# 2101_Version.net
KiCad netlist of a schematic drawn in Altium Designer
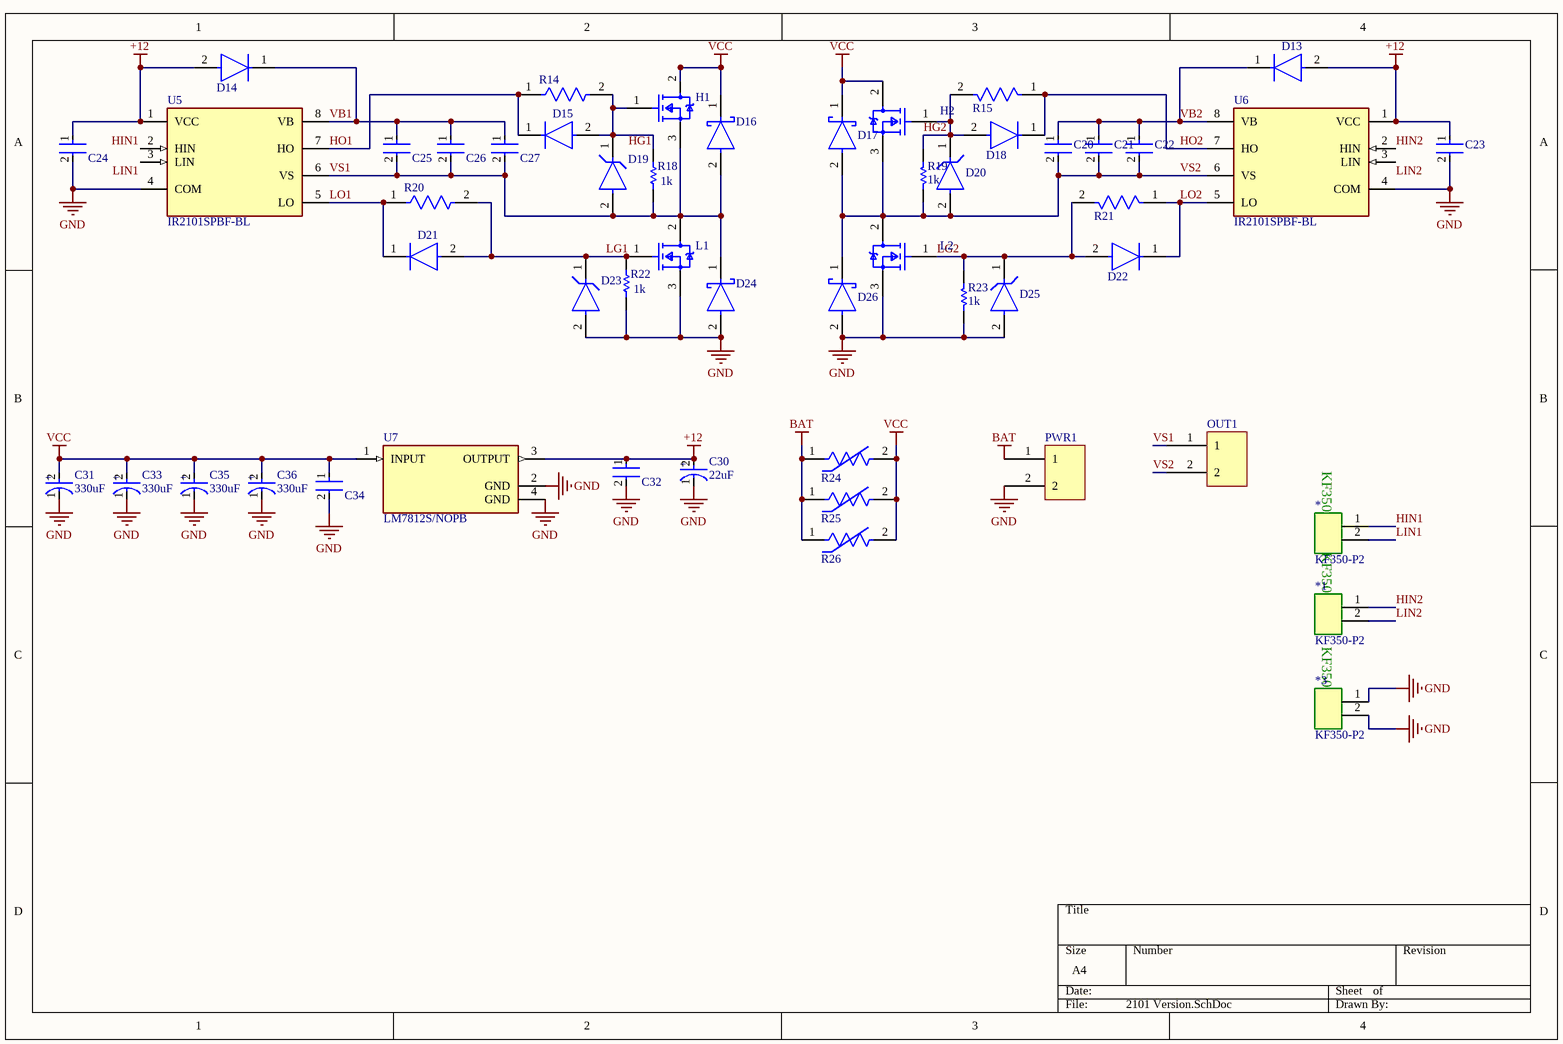
[diagram p0: 2101 Version.SchDoc]

(export (version "E")
  (design (tool "Eeschema 10.0.6"))
  (components
    (comp (ref "*")
      (value "KF350-P2")
      (footprint "New footprint 1")
      (description "3.5mm mini klemens")
      (libsource (lib "ITU Autobee") (part "New symbol 1"))
    )
    (comp (ref "*1")
      (value "KF350-P2")
      (footprint "New footprint 1")
      (description "3.5mm mini klemens")
      (libsource (lib "ITU Autobee") (part "New symbol 1"))
    )
    (comp (ref "*3")
      (value "KF350-P2")
      (footprint "New footprint 1")
      (description "3.5mm mini klemens")
      (libsource (lib "ITU Autobee") (part "New symbol 1"))
    )
    (comp (ref "C20")
      (value "12061C474KAT2A")
      (footprint "FP-1206-L_3_2_0_2-W_1_6_0-IPC_B")
      (description "1206 470 nF 100 V ±10 % Tolerance X7R Surface Mount Multilayer Ceramic Capacitor")
      (libsource (lib "ITU Autobee") (part "b4654b650e69147ec39a6b967a45e02"))
    )
    (comp (ref "C21")
      (value "12061C474KAT2A")
      (footprint "FP-1206-L_3_2_0_2-W_1_6_0-IPC_B")
      (description "1206 470 nF 100 V ±10 % Tolerance X7R Surface Mount Multilayer Ceramic Capacitor")
      (libsource (lib "ITU Autobee") (part "b4654b650e69147ec39a6b967a45e02"))
    )
    (comp (ref "C22")
      (value "12061C474KAT2A")
      (footprint "FP-1206-L_3_2_0_2-W_1_6_0-IPC_B")
      (description "1206 470 nF 100 V ±10 % Tolerance X7R Surface Mount Multilayer Ceramic Capacitor")
      (libsource (lib "ITU Autobee") (part "b4654b650e69147ec39a6b967a45e02"))
    )
    (comp (ref "C23")
      (value "12065C104KAT2A")
      (footprint "FP-1206-L_3_2_0_2-W_1_6_0-IPC_B")
      (description "Ceramic capacitor SMD-1206 100nF /50V X7R# K +-10%, AVX, RoHS, /4000 reel/")
      (libsource (lib "ITU Autobee") (part "02cd4be3c70576c341d710602a673aa"))
    )
    (comp (ref "C24")
      (value "12065C104KAT2A")
      (footprint "FP-1206-L_3_2_0_2-W_1_6_0-IPC_B")
      (description "Ceramic capacitor SMD-1206 100nF /50V X7R# K +-10%, AVX, RoHS, /4000 reel/")
      (libsource (lib "ITU Autobee") (part "02cd4be3c70576c341d710602a673aa"))
    )
    (comp (ref "C25")
      (value "12061C474KAT2A")
      (footprint "FP-1206-L_3_2_0_2-W_1_6_0-IPC_B")
      (description "1206 470 nF 100 V ±10 % Tolerance X7R Surface Mount Multilayer Ceramic Capacitor")
      (libsource (lib "ITU Autobee") (part "b4654b650e69147ec39a6b967a45e02"))
    )
    (comp (ref "C26")
      (value "12061C474KAT2A")
      (footprint "FP-1206-L_3_2_0_2-W_1_6_0-IPC_B")
      (description "1206 470 nF 100 V ±10 % Tolerance X7R Surface Mount Multilayer Ceramic Capacitor")
      (libsource (lib "ITU Autobee") (part "b4654b650e69147ec39a6b967a45e02"))
    )
    (comp (ref "C27")
      (value "12061C474KAT2A")
      (footprint "FP-1206-L_3_2_0_2-W_1_6_0-IPC_B")
      (description "1206 470 nF 100 V ±10 % Tolerance X7R Surface Mount Multilayer Ceramic Capacitor")
      (libsource (lib "ITU Autobee") (part "b4654b650e69147ec39a6b967a45e02"))
    )
    (comp (ref "C30")
      (value "22uF")
      (footprint "FP-SD-MFG")
      (description "Cap Aluminum 22uF 35V 20% (6.3 X 5.4mm) SMD 60mA 2000h 85 C T/R")
      (fields (field (name "Comment") "EEE-1VA220SP 22uF 50V"))
      (libsource (lib "ITU Autobee") (part "a00bbbee19879c290e62620ae7e47b1"))
    )
    (comp (ref "C31")
      (value "330uF")
      (footprint "FP-UWT1V331MNL1GS-MFG")
      (description "Aluminum Electrolytic Capacitor, 330uF 35 V, WT Series 1000h 10 (Dia.) x 10mm")
      (fields (field (name "Comment") "UWT1V331MNL1GS 330uF 35V smd"))
      (libsource (lib "ITU Autobee") (part "203bc49f2ac43e59fd269a8c329ed05"))
    )
    (comp (ref "C32")
      (value "12065C104KAT2A")
      (footprint "FP-1206-L_3_2_0_2-W_1_6_0-IPC_B")
      (description "Ceramic capacitor SMD-1206 100nF /50V X7R# K +-10%, AVX, RoHS, /4000 reel/")
      (libsource (lib "ITU Autobee") (part "02cd4be3c70576c341d710602a673aa"))
    )
    (comp (ref "C33")
      (value "330uF")
      (footprint "FP-UWT1V331MNL1GS-MFG")
      (description "Aluminum Electrolytic Capacitor, 330uF 35 V, WT Series 1000h 10 (Dia.) x 10mm")
      (fields (field (name "Comment") "UWT1V331MNL1GS 330uF 35V smd"))
      (libsource (lib "ITU Autobee") (part "203bc49f2ac43e59fd269a8c329ed05"))
    )
    (comp (ref "C34")
      (value "12065C104KAT2A")
      (footprint "FP-1206-L_3_2_0_2-W_1_6_0-IPC_B")
      (description "Ceramic capacitor SMD-1206 100nF /50V X7R# K +-10%, AVX, RoHS, /4000 reel/")
      (libsource (lib "ITU Autobee") (part "02cd4be3c70576c341d710602a673aa"))
    )
    (comp (ref "C35")
      (value "330uF")
      (footprint "FP-UWT1V331MNL1GS-MFG")
      (description "Aluminum Electrolytic Capacitor, 330uF 35 V, WT Series 1000h 10 (Dia.) x 10mm")
      (fields (field (name "Comment") "UWT1V331MNL1GS 330uF 35V smd"))
      (libsource (lib "ITU Autobee") (part "203bc49f2ac43e59fd269a8c329ed05"))
    )
    (comp (ref "C36")
      (value "330uF")
      (footprint "FP-UWT1V331MNL1GS-MFG")
      (description "Aluminum Electrolytic Capacitor, 330uF 35 V, WT Series 1000h 10 (Dia.) x 10mm")
      (fields (field (name "Comment") "UWT1V331MNL1GS 330uF 35V smd"))
      (libsource (lib "ITU Autobee") (part "203bc49f2ac43e59fd269a8c329ed05"))
    )
    (comp (ref "D13")
      (value "MURS120T3G")
      (footprint "FP-403A-03-MFG")
      (description "VR=200V IF=2A Trr=35ns")
      (libsource (lib "ITU Autobee") (part "d7152d700b627762746794eb795d46e"))
    )
    (comp (ref "D14")
      (value "MURS120T3G")
      (footprint "FP-403A-03-MFG")
      (description "VR=200V IF=2A Trr=35ns")
      (libsource (lib "ITU Autobee") (part "d7152d700b627762746794eb795d46e"))
    )
    (comp (ref "D15")
      (value "MURS120T3G")
      (footprint "FP-403A-03-MFG")
      (description "VR=200V IF=2A Trr=35ns")
      (libsource (lib "ITU Autobee") (part "d7152d700b627762746794eb795d46e"))
    )
    (comp (ref "D16")
      (value "SS34-E3/57T")
      (footprint "FP-95402-MFG")
      (description "DIODE SCHOTTKY 40V 3A DO214AB")
      (libsource (lib "ITU Autobee") (part "1d6ec82d83fb6aee721767c19dac4b9"))
    )
    (comp (ref "D17")
      (value "SS34-E3/57T")
      (footprint "FP-95402-MFG")
      (description "DIODE SCHOTTKY 40V 3A DO214AB")
      (libsource (lib "ITU Autobee") (part "1d6ec82d83fb6aee721767c19dac4b9"))
    )
    (comp (ref "D18")
      (value "MURS120T3G")
      (footprint "FP-403A-03-MFG")
      (description "VR=200V IF=2A Trr=35ns")
      (libsource (lib "ITU Autobee") (part "d7152d700b627762746794eb795d46e"))
    )
    (comp (ref "D19")
      (value "TZMC3V3-GS08")
      (footprint "FP-6_560-5005_01-4-MFG")
      (description "DIODE ZENER 3.3V 500MW SOD80")
      (libsource (lib "ITU Autobee") (part "f813f71cba58e380607f5dd3caf9714"))
    )
    (comp (ref "D20")
      (value "TZMC3V3-GS08")
      (footprint "FP-6_560-5005_01-4-MFG")
      (description "DIODE ZENER 3.3V 500MW SOD80")
      (libsource (lib "ITU Autobee") (part "f813f71cba58e380607f5dd3caf9714"))
    )
    (comp (ref "D21")
      (value "MURS120T3G")
      (footprint "FP-403A-03-MFG")
      (description "VR=200V IF=2A Trr=35ns")
      (libsource (lib "ITU Autobee") (part "d7152d700b627762746794eb795d46e"))
    )
    (comp (ref "D22")
      (value "MURS120T3G")
      (footprint "FP-403A-03-MFG")
      (description "VR=200V IF=2A Trr=35ns")
      (libsource (lib "ITU Autobee") (part "d7152d700b627762746794eb795d46e"))
    )
    (comp (ref "D23")
      (value "TZMC3V3-GS08")
      (footprint "FP-6_560-5005_01-4-MFG")
      (description "DIODE ZENER 3.3V 500MW SOD80")
      (libsource (lib "ITU Autobee") (part "f813f71cba58e380607f5dd3caf9714"))
    )
    (comp (ref "D24")
      (value "SS34-E3/57T")
      (footprint "FP-95402-MFG")
      (description "DIODE SCHOTTKY 40V 3A DO214AB")
      (libsource (lib "ITU Autobee") (part "1d6ec82d83fb6aee721767c19dac4b9"))
    )
    (comp (ref "D25")
      (value "TZMC3V3-GS08")
      (footprint "FP-6_560-5005_01-4-MFG")
      (description "DIODE ZENER 3.3V 500MW SOD80")
      (libsource (lib "ITU Autobee") (part "f813f71cba58e380607f5dd3caf9714"))
    )
    (comp (ref "D26")
      (value "SS34-E3/57T")
      (footprint "FP-95402-MFG")
      (description "DIODE SCHOTTKY 40V 3A DO214AB")
      (libsource (lib "ITU Autobee") (part "1d6ec82d83fb6aee721767c19dac4b9"))
    )
    (comp (ref "H1")
      (value "IRF3205STRLPBF")
      (footprint "FP-PG-TO263-3-MFG")
      (description "MOSFET N-CH 55V 110A D2PAK")
      (libsource (lib "ITU Autobee") (part "b09f7f152735e370c1ea22a33fa83d6"))
    )
    (comp (ref "H2")
      (value "IRF3205STRLPBF")
      (footprint "FP-PG-TO263-3-MFG")
      (description "MOSFET N-CH 55V 110A D2PAK")
      (libsource (lib "ITU Autobee") (part "b09f7f152735e370c1ea22a33fa83d6"))
    )
    (comp (ref "L1")
      (value "IRF3205STRLPBF")
      (footprint "FP-PG-TO263-3-MFG")
      (description "MOSFET N-CH 55V 110A D2PAK")
      (libsource (lib "ITU Autobee") (part "b09f7f152735e370c1ea22a33fa83d6"))
    )
    (comp (ref "L2")
      (value "IRF3205STRLPBF")
      (footprint "FP-PG-TO263-3-MFG")
      (description "MOSFET N-CH 55V 110A D2PAK")
      (libsource (lib "ITU Autobee") (part "b09f7f152735e370c1ea22a33fa83d6"))
    )
    (comp (ref "OUT1")
      (value "2 pin terminal klemens")
      (footprint "New footprint 1")
      (description "2 pin terminal klemens pin aralığı 200 mil")
      (libsource (lib "ITU Autobee") (part "2 pin terminal klemens schematic"))
    )
    (comp (ref "PWR1")
      (value "2 pin terminal klemens")
      (footprint "New footprint 1")
      (description "2 pin terminal klemens pin aralığı 200 mil")
      (libsource (lib "ITU Autobee") (part "2 pin terminal klemens schematic"))
    )
    (comp (ref "R14")
      (value "RC1206JR-0710RL")
      (footprint "FP-RC1206-0_65-MFG")
      (description "Res General Purpose Thick Film 1206 10 Ohm 5% 1/4W ±200ppm/°C Molded SMD Paper T/R")
      (libsource (lib "ITU Autobee") (part "8db39607336c341a927600551d01821"))
    )
    (comp (ref "R15")
      (value "RC1206JR-0710RL")
      (footprint "FP-RC1206-0_65-MFG")
      (description "Res General Purpose Thick Film 1206 10 Ohm 5% 1/4W ±200ppm/°C Molded SMD Paper T/R")
      (libsource (lib "ITU Autobee") (part "8db39607336c341a927600551d01821"))
    )
    (comp (ref "R18")
      (value "1k")
      (footprint "RESC3116X70X50ML13T20")
      (description "Chip Resistor, 1 KOhm, +/- 1%, 0.25 W, -55 to 155 degC, 1206 (3216 Metric)")
      (fields (field (name "TOLERANCE") "1%") (field (name "POWER") "250mW"))
      (libsource (lib "ITU Autobee") (part "RES-2"))
    )
    (comp (ref "R19")
      (value "1k")
      (footprint "RESC3116X70X50ML13T20")
      (description "Chip Resistor, 1 KOhm, +/- 1%, 0.25 W, -55 to 155 degC, 1206 (3216 Metric)")
      (fields (field (name "TOLERANCE") "1%") (field (name "POWER") "250mW"))
      (libsource (lib "ITU Autobee") (part "RES-2"))
    )
    (comp (ref "R20")
      (value "RC1206JR-0710RL")
      (footprint "FP-RC1206-0_65-MFG")
      (description "Res General Purpose Thick Film 1206 10 Ohm 5% 1/4W ±200ppm/°C Molded SMD Paper T/R")
      (libsource (lib "ITU Autobee") (part "8db39607336c341a927600551d01821"))
    )
    (comp (ref "R21")
      (value "RC1206JR-0710RL")
      (footprint "FP-RC1206-0_65-MFG")
      (description "Res General Purpose Thick Film 1206 10 Ohm 5% 1/4W ±200ppm/°C Molded SMD Paper T/R")
      (libsource (lib "ITU Autobee") (part "8db39607336c341a927600551d01821"))
    )
    (comp (ref "R22")
      (value "1k")
      (footprint "RESC3116X70X50ML13T20")
      (description "Chip Resistor, 1 KOhm, +/- 1%, 0.25 W, -55 to 155 degC, 1206 (3216 Metric)")
      (fields (field (name "TOLERANCE") "1%") (field (name "POWER") "250mW"))
      (libsource (lib "ITU Autobee") (part "RES-2"))
    )
    (comp (ref "R23")
      (value "1k")
      (footprint "RESC3116X70X50ML13T20")
      (description "Chip Resistor, 1 KOhm, +/- 1%, 0.25 W, -55 to 155 degC, 1206 (3216 Metric)")
      (fields (field (name "TOLERANCE") "1%") (field (name "POWER") "250mW"))
      (libsource (lib "ITU Autobee") (part "RES-2"))
    )
    (comp (ref "R24")
      (value "20mm Body 7.5mm pitch Thermistor")
      (footprint "FP-NTPAD-MFG")
      (libsource (lib "ITU Autobee") (part "3b148a6ebabc5fb4d708a66c052d352"))
    )
    (comp (ref "R25")
      (value "20mm Body 7.5mm pitch Thermistor")
      (footprint "FP-NTPAD-MFG")
      (libsource (lib "ITU Autobee") (part "3b148a6ebabc5fb4d708a66c052d352"))
    )
    (comp (ref "R26")
      (value "20mm Body 7.5mm pitch Thermistor")
      (footprint "FP-NTPAD-MFG")
      (libsource (lib "ITU Autobee") (part "3b148a6ebabc5fb4d708a66c052d352"))
    )
    (comp (ref "U5")
      (value "IR2101SPBF-BL")
      (footprint "FP-PG-DSO-8-MFG")
      (description "MOSFET DRVR 600V 0.36A 2-OUT Hi/Lo Side Non-Inv 8-Pin SOIC")
      (libsource (lib "") (part "434b8f4246b9711489e8709b290a301_1"))
    )
    (comp (ref "U6")
      (value "IR2101SPBF-BL")
      (footprint "FP-PG-DSO-8-MFG")
      (description "MOSFET DRVR 600V 0.36A 2-OUT Hi/Lo Side Non-Inv 8-Pin SOIC")
      (libsource (lib "ITU Autobee") (part "434b8f4246b9711489e8709b290a301"))
    )
    (comp (ref "U7")
      (value "LM7812S/NOPB")
      (footprint "FP-KTT0003B-MFG")
      (description "IC REG LINEAR 12V 1.5A")
      (libsource (lib "Altium Content Vault") (part "6590f56fc76c1ccc3d91a0358e41599"))
    )
  )
  (nets
    (net (code "1") (name "+12") (class "Default")
      (node (ref "C23") (pin "1") (pinfunction "1_1") (pintype "passive"))
      (node (ref "C24") (pin "1") (pinfunction "1_1") (pintype "passive"))
      (node (ref "C30") (pin "2") (pinfunction "A_2") (pintype "passive"))
      (node (ref "C32") (pin "1") (pinfunction "1_1") (pintype "passive"))
      (node (ref "D13") (pin "2") (pinfunction "A_2") (pintype "passive"))
      (node (ref "D14") (pin "2") (pinfunction "A_2") (pintype "passive"))
      (node (ref "U5") (pin "1") (pinfunction "VCC_1") (pintype "power_in"))
      (node (ref "U6") (pin "1") (pinfunction "VCC_1") (pintype "power_in"))
      (node (ref "U7") (pin "3") (pinfunction "OUTPUT_3") (pintype "output"))
    )
    (net (code "2") (name "/HG1") (class "Default")
      (node (ref "D15") (pin "2") (pinfunction "A_2") (pintype "passive"))
      (node (ref "D19") (pin "1") (pinfunction "C_1") (pintype "passive"))
      (node (ref "H1") (pin "1") (pinfunction "G_1") (pintype "passive"))
      (node (ref "R14") (pin "2") (pinfunction "2_2") (pintype "passive"))
      (node (ref "R18") (pin "1") (pinfunction "1_1") (pintype "passive"))
    )
    (net (code "3") (name "/HG2") (class "Default")
      (node (ref "D18") (pin "2") (pinfunction "A_2") (pintype "passive"))
      (node (ref "D20") (pin "1") (pinfunction "C_1") (pintype "passive"))
      (node (ref "H2") (pin "1") (pinfunction "G_1") (pintype "passive"))
      (node (ref "R15") (pin "2") (pinfunction "2_2") (pintype "passive"))
      (node (ref "R19") (pin "1") (pinfunction "1_1") (pintype "passive"))
    )
    (net (code "4") (name "/HIN1") (class "Default")
      (node (ref "*") (pin "1") (pinfunction "1_1") (pintype "passive"))
      (node (ref "U5") (pin "2") (pinfunction "HIN_2") (pintype "input"))
    )
    (net (code "5") (name "/HIN2") (class "Default")
      (node (ref "*1") (pin "1") (pinfunction "1_1") (pintype "passive"))
      (node (ref "U6") (pin "2") (pinfunction "HIN_2") (pintype "input"))
    )
    (net (code "6") (name "/HO1") (class "Default")
      (node (ref "D15") (pin "1") (pinfunction "C_1") (pintype "passive"))
      (node (ref "R14") (pin "1") (pinfunction "1_1") (pintype "passive"))
      (node (ref "U5") (pin "7") (pinfunction "HO_7") (pintype "passive"))
    )
    (net (code "7") (name "/HO2") (class "Default")
      (node (ref "D18") (pin "1") (pinfunction "C_1") (pintype "passive"))
      (node (ref "R15") (pin "1") (pinfunction "1_1") (pintype "passive"))
      (node (ref "U6") (pin "7") (pinfunction "HO_7") (pintype "passive"))
    )
    (net (code "8") (name "/LG1") (class "Default")
      (node (ref "D21") (pin "2") (pinfunction "A_2") (pintype "passive"))
      (node (ref "D23") (pin "1") (pinfunction "C_1") (pintype "passive"))
      (node (ref "L1") (pin "1") (pinfunction "G_1") (pintype "passive"))
      (node (ref "R20") (pin "2") (pinfunction "2_2") (pintype "passive"))
      (node (ref "R22") (pin "1") (pinfunction "1_1") (pintype "passive"))
    )
    (net (code "9") (name "/LG2") (class "Default")
      (node (ref "D22") (pin "2") (pinfunction "A_2") (pintype "passive"))
      (node (ref "D25") (pin "1") (pinfunction "C_1") (pintype "passive"))
      (node (ref "L2") (pin "1") (pinfunction "G_1") (pintype "passive"))
      (node (ref "R21") (pin "2") (pinfunction "2_2") (pintype "passive"))
      (node (ref "R23") (pin "1") (pinfunction "1_1") (pintype "passive"))
    )
    (net (code "10") (name "/LIN1") (class "Default")
      (node (ref "*") (pin "2") (pinfunction "2_2") (pintype "passive"))
      (node (ref "U5") (pin "3") (pinfunction "LIN_3") (pintype "input"))
    )
    (net (code "11") (name "/LIN2") (class "Default")
      (node (ref "*1") (pin "2") (pinfunction "2_2") (pintype "passive"))
      (node (ref "U6") (pin "3") (pinfunction "LIN_3") (pintype "input"))
    )
    (net (code "12") (name "/LO1") (class "Default")
      (node (ref "D21") (pin "1") (pinfunction "C_1") (pintype "passive"))
      (node (ref "R20") (pin "1") (pinfunction "1_1") (pintype "passive"))
      (node (ref "U5") (pin "5") (pinfunction "LO_5") (pintype "passive"))
    )
    (net (code "13") (name "/LO2") (class "Default")
      (node (ref "D22") (pin "1") (pinfunction "C_1") (pintype "passive"))
      (node (ref "R21") (pin "1") (pinfunction "1_1") (pintype "passive"))
      (node (ref "U6") (pin "5") (pinfunction "LO_5") (pintype "passive"))
    )
    (net (code "14") (name "/VB1") (class "Default")
      (node (ref "C25") (pin "1") (pinfunction "1_1") (pintype "passive"))
      (node (ref "C26") (pin "1") (pinfunction "1_1") (pintype "passive"))
      (node (ref "C27") (pin "1") (pinfunction "1_1") (pintype "passive"))
      (node (ref "D14") (pin "1") (pinfunction "C_1") (pintype "passive"))
      (node (ref "U5") (pin "8") (pinfunction "VB_8") (pintype "power_in"))
    )
    (net (code "15") (name "/VB2") (class "Default")
      (node (ref "C20") (pin "1") (pinfunction "1_1") (pintype "passive"))
      (node (ref "C21") (pin "1") (pinfunction "1_1") (pintype "passive"))
      (node (ref "C22") (pin "1") (pinfunction "1_1") (pintype "passive"))
      (node (ref "D13") (pin "1") (pinfunction "C_1") (pintype "passive"))
      (node (ref "U6") (pin "8") (pinfunction "VB_8") (pintype "power_in"))
    )
    (net (code "16") (name "/VS1") (class "Default")
      (node (ref "C25") (pin "2") (pinfunction "2_2") (pintype "passive"))
      (node (ref "C26") (pin "2") (pinfunction "2_2") (pintype "passive"))
      (node (ref "C27") (pin "2") (pinfunction "2_2") (pintype "passive"))
      (node (ref "D16") (pin "2") (pinfunction "A_2") (pintype "passive"))
      (node (ref "D19") (pin "2") (pinfunction "A_2") (pintype "passive"))
      (node (ref "D24") (pin "1") (pinfunction "C_1") (pintype "passive"))
      (node (ref "H1") (pin "3") (pinfunction "S_3") (pintype "passive"))
      (node (ref "L1") (pin "2") (pinfunction "D_2") (pintype "passive"))
      (node (ref "OUT1") (pin "1") (pinfunction "1_1") (pintype "passive"))
      (node (ref "R18") (pin "2") (pinfunction "2_2") (pintype "passive"))
      (node (ref "U5") (pin "6") (pinfunction "VS_6") (pintype "power_in"))
    )
    (net (code "17") (name "/VS2") (class "Default")
      (node (ref "C20") (pin "2") (pinfunction "2_2") (pintype "passive"))
      (node (ref "C21") (pin "2") (pinfunction "2_2") (pintype "passive"))
      (node (ref "C22") (pin "2") (pinfunction "2_2") (pintype "passive"))
      (node (ref "D17") (pin "2") (pinfunction "A_2") (pintype "passive"))
      (node (ref "D20") (pin "2") (pinfunction "A_2") (pintype "passive"))
      (node (ref "D26") (pin "1") (pinfunction "C_1") (pintype "passive"))
      (node (ref "H2") (pin "3") (pinfunction "S_3") (pintype "passive"))
      (node (ref "L2") (pin "2") (pinfunction "D_2") (pintype "passive"))
      (node (ref "OUT1") (pin "2") (pinfunction "2_2") (pintype "passive"))
      (node (ref "R19") (pin "2") (pinfunction "2_2") (pintype "passive"))
      (node (ref "U6") (pin "6") (pinfunction "VS_6") (pintype "power_in"))
    )
    (net (code "18") (name "BAT") (class "Default")
      (node (ref "PWR1") (pin "1") (pinfunction "1_1") (pintype "passive"))
      (node (ref "R24") (pin "1") (pinfunction "1_1") (pintype "passive"))
      (node (ref "R25") (pin "1") (pinfunction "1_1") (pintype "passive"))
      (node (ref "R26") (pin "1") (pinfunction "1_1") (pintype "passive"))
    )
    (net (code "19") (name "GND") (class "Default")
      (node (ref "*3") (pin "1") (pinfunction "1_1") (pintype "passive"))
      (node (ref "*3") (pin "2") (pinfunction "2_2") (pintype "passive"))
      (node (ref "C23") (pin "2") (pinfunction "2_2") (pintype "passive"))
      (node (ref "C24") (pin "2") (pinfunction "2_2") (pintype "passive"))
      (node (ref "C30") (pin "1") (pinfunction "C_1") (pintype "passive"))
      (node (ref "C31") (pin "1") (pinfunction "C_1") (pintype "passive"))
      (node (ref "C32") (pin "2") (pinfunction "2_2") (pintype "passive"))
      (node (ref "C33") (pin "1") (pinfunction "C_1") (pintype "passive"))
      (node (ref "C34") (pin "2") (pinfunction "2_2") (pintype "passive"))
      (node (ref "C35") (pin "1") (pinfunction "C_1") (pintype "passive"))
      (node (ref "C36") (pin "1") (pinfunction "C_1") (pintype "passive"))
      (node (ref "D23") (pin "2") (pinfunction "A_2") (pintype "passive"))
      (node (ref "D24") (pin "2") (pinfunction "A_2") (pintype "passive"))
      (node (ref "D25") (pin "2") (pinfunction "A_2") (pintype "passive"))
      (node (ref "D26") (pin "2") (pinfunction "A_2") (pintype "passive"))
      (node (ref "L1") (pin "3") (pinfunction "S_3") (pintype "passive"))
      (node (ref "L2") (pin "3") (pinfunction "S_3") (pintype "passive"))
      (node (ref "PWR1") (pin "2") (pinfunction "2_2") (pintype "passive"))
      (node (ref "R22") (pin "2") (pinfunction "2_2") (pintype "passive"))
      (node (ref "R23") (pin "2") (pinfunction "2_2") (pintype "passive"))
      (node (ref "U5") (pin "4") (pinfunction "COM_4") (pintype "passive"))
      (node (ref "U6") (pin "4") (pinfunction "COM_4") (pintype "passive"))
      (node (ref "U7") (pin "2") (pinfunction "GND_2") (pintype "power_in"))
      (node (ref "U7") (pin "4") (pinfunction "GND_4") (pintype "power_in"))
    )
    (net (code "20") (name "VCC") (class "Default")
      (node (ref "C31") (pin "2") (pinfunction "A_2") (pintype "passive"))
      (node (ref "C33") (pin "2") (pinfunction "A_2") (pintype "passive"))
      (node (ref "C34") (pin "1") (pinfunction "1_1") (pintype "passive"))
      (node (ref "C35") (pin "2") (pinfunction "A_2") (pintype "passive"))
      (node (ref "C36") (pin "2") (pinfunction "A_2") (pintype "passive"))
      (node (ref "D16") (pin "1") (pinfunction "C_1") (pintype "passive"))
      (node (ref "D17") (pin "1") (pinfunction "C_1") (pintype "passive"))
      (node (ref "H1") (pin "2") (pinfunction "D_2") (pintype "passive"))
      (node (ref "H2") (pin "2") (pinfunction "D_2") (pintype "passive"))
      (node (ref "R24") (pin "2") (pinfunction "2_2") (pintype "passive"))
      (node (ref "R25") (pin "2") (pinfunction "2_2") (pintype "passive"))
      (node (ref "R26") (pin "2") (pinfunction "2_2") (pintype "passive"))
      (node (ref "U7") (pin "1") (pinfunction "INPUT_1") (pintype "input"))
    )
  )
)
